# controllerLayoutSchematic.net
KiCad netlist of a schematic drawn in EAGLE
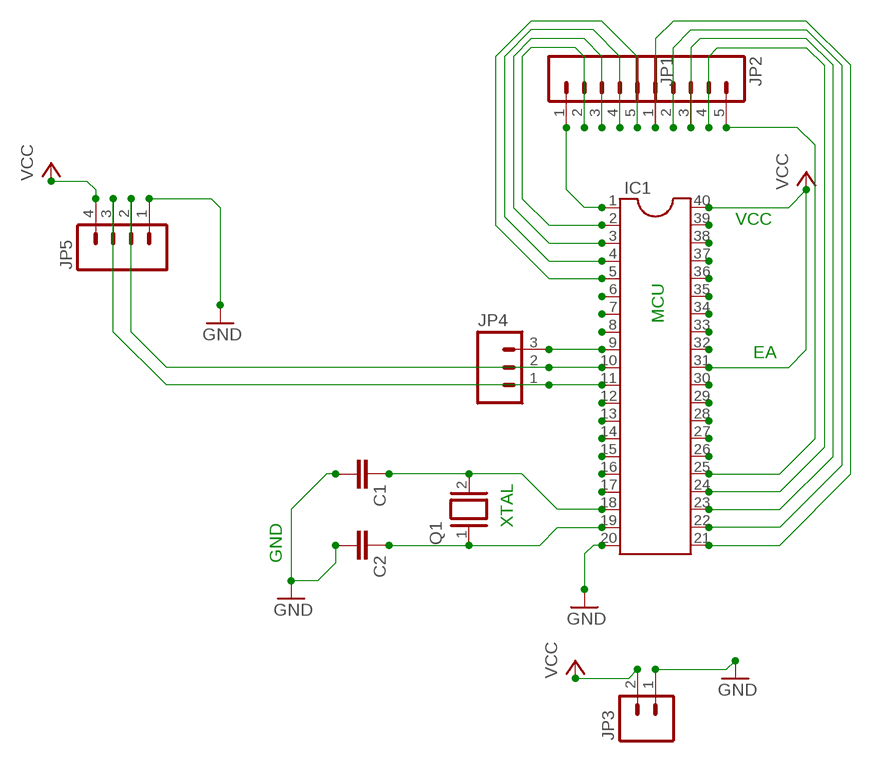
[diagram p0: schematic, sheet 1]

(export (version "E")
  (design (tool "Eeschema 10.0.6"))
  (components
    (comp (ref "C1")
      (value "CAPPTH2")
      (footprint "eagle-import:CAP-PTH-SMALL2")
      (libsource (lib "eagle-import") (part "CAPPTH2"))
    )
    (comp (ref "C2")
      (value "CAPPTH2")
      (footprint "eagle-import:CAP-PTH-SMALL2")
      (libsource (lib "eagle-import") (part "CAPPTH2"))
    )
    (comp (ref "IC1")
      (value "DIL40")
      (footprint "eagle-import:DIL40")
      (libsource (lib "eagle-import") (part "DIL40"))
    )
    (comp (ref "JP1")
      (value "M05PTH_LONGPADS")
      (footprint "eagle-import:1X05_LONGPADS")
      (libsource (lib "eagle-import") (part "M05PTH_LONGPADS"))
    )
    (comp (ref "JP2")
      (value "M05PTH_LONGPADS")
      (footprint "eagle-import:1X05_LONGPADS")
      (libsource (lib "eagle-import") (part "M05PTH_LONGPADS"))
    )
    (comp (ref "JP3")
      (value "M02PTH3")
      (footprint "eagle-import:1X02_LONGPADS")
      (libsource (lib "eagle-import") (part "M02PTH3"))
    )
    (comp (ref "JP4")
      (value "M03LONGPADS")
      (footprint "eagle-import:1X03_LONGPADS")
      (libsource (lib "eagle-import") (part "M03LONGPADS"))
    )
    (comp (ref "JP5")
      (value "M04SMD")
      (footprint "eagle-import:1X04-SMD")
      (libsource (lib "eagle-import") (part "M04SMD"))
    )
    (comp (ref "Q1")
      (value "XTAL")
      (footprint "eagle-import:Q")
      (libsource (lib "eagle-import") (part "XTAL"))
    )
  )
  (nets
    (net (code "1") (name "GND") (class "Default")
      (node (ref "C1") (pin "2") (pinfunction "2_2") (pintype "passive"))
      (node (ref "C2") (pin "2") (pinfunction "2_2") (pintype "passive"))
      (node (ref "IC1") (pin "20") (pinfunction "20_20") (pintype "passive"))
      (node (ref "JP3") (pin "1") (pinfunction "1_1") (pintype "passive"))
      (node (ref "JP5") (pin "1") (pinfunction "1_1") (pintype "passive"))
    )
    (net (code "2") (name "Net-(C1-Pad1)") (class "Default")
      (node (ref "C1") (pin "1") (pinfunction "1_1") (pintype "passive"))
      (node (ref "IC1") (pin "18") (pinfunction "18_18") (pintype "passive"))
      (node (ref "Q1") (pin "2") (pinfunction "2_2") (pintype "passive"))
    )
    (net (code "3") (name "Net-(C2-Pad1)") (class "Default")
      (node (ref "C2") (pin "1") (pinfunction "1_1") (pintype "passive"))
      (node (ref "IC1") (pin "19") (pinfunction "19_19") (pintype "passive"))
      (node (ref "Q1") (pin "1") (pinfunction "1_1") (pintype "passive"))
    )
    (net (code "4") (name "Net-(IC1-Pad1)") (class "Default")
      (node (ref "IC1") (pin "1") (pinfunction "1_1") (pintype "passive"))
      (node (ref "JP1") (pin "1") (pinfunction "1_1") (pintype "passive"))
    )
    (net (code "5") (name "Net-(IC1-Pad2)") (class "Default")
      (node (ref "IC1") (pin "2") (pinfunction "2_2") (pintype "passive"))
      (node (ref "JP1") (pin "2") (pinfunction "2_2") (pintype "passive"))
    )
    (net (code "6") (name "Net-(IC1-Pad3)") (class "Default")
      (node (ref "IC1") (pin "3") (pinfunction "3_3") (pintype "passive"))
      (node (ref "JP1") (pin "3") (pinfunction "3_3") (pintype "passive"))
    )
    (net (code "7") (name "Net-(IC1-Pad4)") (class "Default")
      (node (ref "IC1") (pin "4") (pinfunction "4_4") (pintype "passive"))
      (node (ref "JP1") (pin "4") (pinfunction "4_4") (pintype "passive"))
    )
    (net (code "8") (name "Net-(IC1-Pad5)") (class "Default")
      (node (ref "IC1") (pin "5") (pinfunction "5_5") (pintype "passive"))
      (node (ref "JP1") (pin "5") (pinfunction "5_5") (pintype "passive"))
    )
    (net (code "9") (name "Net-(IC1-Pad9)") (class "Default")
      (node (ref "IC1") (pin "9") (pinfunction "9_9") (pintype "passive"))
      (node (ref "JP4") (pin "3") (pinfunction "3_3") (pintype "passive"))
    )
    (net (code "10") (name "Net-(IC1-Pad10)") (class "Default")
      (node (ref "IC1") (pin "10") (pinfunction "10_10") (pintype "passive"))
      (node (ref "JP4") (pin "2") (pinfunction "2_2") (pintype "passive"))
      (node (ref "JP5") (pin "2") (pinfunction "2_2") (pintype "passive"))
    )
    (net (code "11") (name "Net-(IC1-Pad11)") (class "Default")
      (node (ref "IC1") (pin "11") (pinfunction "11_11") (pintype "passive"))
      (node (ref "JP4") (pin "1") (pinfunction "1_1") (pintype "passive"))
      (node (ref "JP5") (pin "3") (pinfunction "3_3") (pintype "passive"))
    )
    (net (code "12") (name "Net-(IC1-Pad21)") (class "Default")
      (node (ref "IC1") (pin "21") (pinfunction "21_21") (pintype "passive"))
      (node (ref "JP2") (pin "1") (pinfunction "1_1") (pintype "passive"))
    )
    (net (code "13") (name "Net-(IC1-Pad22)") (class "Default")
      (node (ref "IC1") (pin "22") (pinfunction "22_22") (pintype "passive"))
      (node (ref "JP2") (pin "2") (pinfunction "2_2") (pintype "passive"))
    )
    (net (code "14") (name "Net-(IC1-Pad23)") (class "Default")
      (node (ref "IC1") (pin "23") (pinfunction "23_23") (pintype "passive"))
      (node (ref "JP2") (pin "3") (pinfunction "3_3") (pintype "passive"))
    )
    (net (code "15") (name "Net-(IC1-Pad24)") (class "Default")
      (node (ref "IC1") (pin "24") (pinfunction "24_24") (pintype "passive"))
      (node (ref "JP2") (pin "4") (pinfunction "4_4") (pintype "passive"))
    )
    (net (code "16") (name "Net-(IC1-Pad25)") (class "Default")
      (node (ref "IC1") (pin "25") (pinfunction "25_25") (pintype "passive"))
      (node (ref "JP2") (pin "5") (pinfunction "5_5") (pintype "passive"))
    )
    (net (code "17") (name "VCC") (class "Default")
      (node (ref "IC1") (pin "31") (pinfunction "31_31") (pintype "passive"))
      (node (ref "IC1") (pin "40") (pinfunction "40_40") (pintype "passive"))
      (node (ref "JP3") (pin "2") (pinfunction "2_2") (pintype "passive"))
      (node (ref "JP5") (pin "4") (pinfunction "4_4") (pintype "passive"))
    )
    (net (code "18") (name "unconnected-(IC1-Pad6)") (class "Default")
      (node (ref "IC1") (pin "6") (pinfunction "6_6") (pintype "passive"))
    )
    (net (code "19") (name "unconnected-(IC1-Pad7)") (class "Default")
      (node (ref "IC1") (pin "7") (pinfunction "7_7") (pintype "passive"))
    )
    (net (code "20") (name "unconnected-(IC1-Pad8)") (class "Default")
      (node (ref "IC1") (pin "8") (pinfunction "8_8") (pintype "passive"))
    )
    (net (code "21") (name "unconnected-(IC1-Pad12)") (class "Default")
      (node (ref "IC1") (pin "12") (pinfunction "12_12") (pintype "passive"))
    )
    (net (code "22") (name "unconnected-(IC1-Pad13)") (class "Default")
      (node (ref "IC1") (pin "13") (pinfunction "13_13") (pintype "passive"))
    )
    (net (code "23") (name "unconnected-(IC1-Pad14)") (class "Default")
      (node (ref "IC1") (pin "14") (pinfunction "14_14") (pintype "passive"))
    )
    (net (code "24") (name "unconnected-(IC1-Pad15)") (class "Default")
      (node (ref "IC1") (pin "15") (pinfunction "15_15") (pintype "passive"))
    )
    (net (code "25") (name "unconnected-(IC1-Pad16)") (class "Default")
      (node (ref "IC1") (pin "16") (pinfunction "16_16") (pintype "passive"))
    )
    (net (code "26") (name "unconnected-(IC1-Pad17)") (class "Default")
      (node (ref "IC1") (pin "17") (pinfunction "17_17") (pintype "passive"))
    )
    (net (code "27") (name "unconnected-(IC1-Pad26)") (class "Default")
      (node (ref "IC1") (pin "26") (pinfunction "26_26") (pintype "passive"))
    )
    (net (code "28") (name "unconnected-(IC1-Pad27)") (class "Default")
      (node (ref "IC1") (pin "27") (pinfunction "27_27") (pintype "passive"))
    )
    (net (code "29") (name "unconnected-(IC1-Pad28)") (class "Default")
      (node (ref "IC1") (pin "28") (pinfunction "28_28") (pintype "passive"))
    )
    (net (code "30") (name "unconnected-(IC1-Pad29)") (class "Default")
      (node (ref "IC1") (pin "29") (pinfunction "29_29") (pintype "passive"))
    )
    (net (code "31") (name "unconnected-(IC1-Pad30)") (class "Default")
      (node (ref "IC1") (pin "30") (pinfunction "30_30") (pintype "passive"))
    )
    (net (code "32") (name "unconnected-(IC1-Pad32)") (class "Default")
      (node (ref "IC1") (pin "32") (pinfunction "32_32") (pintype "passive"))
    )
    (net (code "33") (name "unconnected-(IC1-Pad33)") (class "Default")
      (node (ref "IC1") (pin "33") (pinfunction "33_33") (pintype "passive"))
    )
    (net (code "34") (name "unconnected-(IC1-Pad34)") (class "Default")
      (node (ref "IC1") (pin "34") (pinfunction "34_34") (pintype "passive"))
    )
    (net (code "35") (name "unconnected-(IC1-Pad35)") (class "Default")
      (node (ref "IC1") (pin "35") (pinfunction "35_35") (pintype "passive"))
    )
    (net (code "36") (name "unconnected-(IC1-Pad36)") (class "Default")
      (node (ref "IC1") (pin "36") (pinfunction "36_36") (pintype "passive"))
    )
    (net (code "37") (name "unconnected-(IC1-Pad37)") (class "Default")
      (node (ref "IC1") (pin "37") (pinfunction "37_37") (pintype "passive"))
    )
    (net (code "38") (name "unconnected-(IC1-Pad38)") (class "Default")
      (node (ref "IC1") (pin "38") (pinfunction "38_38") (pintype "passive"))
    )
    (net (code "39") (name "unconnected-(IC1-Pad39)") (class "Default")
      (node (ref "IC1") (pin "39") (pinfunction "39_39") (pintype "passive"))
    )
  )
)
